# Power_Supply.net
KiCad netlist of a schematic drawn in Altium Designer
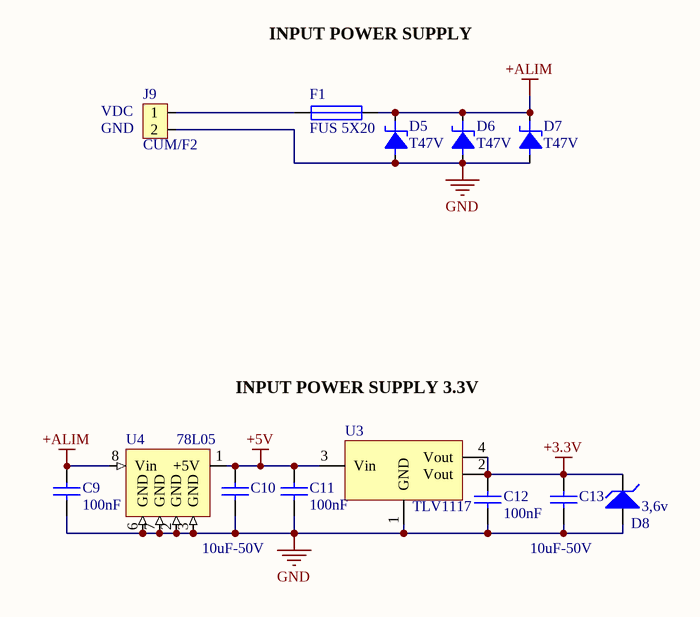
[diagram p0: Power_Supply.SchDoc]

(export (version "E")
  (design (tool "Eeschema 10.0.6"))
  (components
    (comp (ref "C9")
      (value "100nF")
      (footprint "C0603")
      (description "Capacitor")
      (libsource (lib "MyLibrary") (part "Cap"))
    )
    (comp (ref "C10")
      (value "10uF-50V")
      (footprint "C1206")
      (description "Capacitor")
      (libsource (lib "MyLibrary") (part "Cap"))
    )
    (comp (ref "C11")
      (value "100nF")
      (footprint "C0603")
      (description "Capacitor")
      (libsource (lib "MyLibrary") (part "Cap"))
    )
    (comp (ref "C12")
      (value "100nF")
      (footprint "C0603")
      (description "Capacitor")
      (libsource (lib "MyLibrary") (part "Cap"))
    )
    (comp (ref "C13")
      (value "10uF-50V")
      (footprint "C1206")
      (description "Capacitor")
      (libsource (lib "MyLibrary") (part "Cap"))
    )
    (comp (ref "D5")
      (value "T47V")
      (footprint "DIO47A")
      (description "TRANSIL CMS 47V unidirectionnelle")
      (libsource (lib "PROTEL") (part "T47V"))
    )
    (comp (ref "D6")
      (value "T47V")
      (footprint "DIO47A")
      (description "TRANSIL CMS 47V unidirectionnelle")
      (libsource (lib "PROTEL") (part "T47V"))
    )
    (comp (ref "D7")
      (value "T47V")
      (footprint "DIO47A")
      (description "TRANSIL CMS 47V unidirectionnelle")
      (libsource (lib "PROTEL") (part "T47V"))
    )
    (comp (ref "D8")
      (value "3,6v")
      (footprint "SOD123")
      (description "Zener Diode")
      (libsource (lib "MyLibrary") (part "D Zener"))
    )
    (comp (ref "F1")
      (value "FUS 5X20")
      (footprint "FUSPO-A1")
      (description "FUSIBLE VERRE 5 x 20")
      (libsource (lib "PROTEL") (part "FUS 5X20"))
    )
    (comp (ref "J9")
      (value "CUM/F2")
      (footprint "CNT2H")
      (description "connecteur  2 points")
      (libsource (lib "PROTEL") (part "CUM/F2"))
    )
    (comp (ref "U3")
      (value "TLV1117")
      (footprint "SOT223")
      (description "LDO regulator 3.3V")
      (libsource (lib "MyLibrary") (part "TLV1117"))
    )
    (comp (ref "U4")
      (value "78L05")
      (footprint "REG5VE")
      (description "E:cms ;C1:faible conso; VD:TO220 debout;")
      (libsource (lib "PROTEL") (part "78L05"))
    )
  )
  (nets
    (net (code "1") (name "+3.3V") (class "Default")
      (node (ref "C12") (pin "1") (pinfunction "1_1") (pintype "passive"))
      (node (ref "C13") (pin "2") (pinfunction "2_2") (pintype "passive"))
      (node (ref "D8") (pin "2") (pinfunction "K_2") (pintype "passive"))
      (node (ref "U3") (pin "2") (pinfunction "Vout_2") (pintype "passive"))
      (node (ref "U3") (pin "4") (pinfunction "Vout_4") (pintype "passive"))
    )
    (net (code "2") (name "+5V") (class "Default")
      (node (ref "C10") (pin "2") (pinfunction "2_2") (pintype "passive"))
      (node (ref "C11") (pin "1") (pinfunction "1_1") (pintype "passive"))
      (node (ref "U3") (pin "3") (pinfunction "Vin_3") (pintype "passive"))
      (node (ref "U4") (pin "1") (pinfunction "+5V_1") (pintype "power_in"))
    )
    (net (code "3") (name "+ALIM") (class "Default")
      (node (ref "C9") (pin "1") (pinfunction "1_1") (pintype "passive"))
      (node (ref "D5") (pin "1") (pintype "passive"))
      (node (ref "D6") (pin "1") (pintype "passive"))
      (node (ref "D7") (pin "1") (pintype "passive"))
      (node (ref "F1") (pin "2") (pintype "passive"))
      (node (ref "U4") (pin "8") (pinfunction "Vin_8") (pintype "input"))
    )
    (net (code "4") (name "GND") (class "Default")
      (node (ref "C10") (pin "1") (pinfunction "1_1") (pintype "passive"))
      (node (ref "C11") (pin "2") (pinfunction "2_2") (pintype "passive"))
      (node (ref "C12") (pin "2") (pinfunction "2_2") (pintype "passive"))
      (node (ref "C13") (pin "1") (pinfunction "1_1") (pintype "passive"))
      (node (ref "C9") (pin "2") (pinfunction "2_2") (pintype "passive"))
      (node (ref "D5") (pin "2") (pintype "passive"))
      (node (ref "D6") (pin "2") (pintype "passive"))
      (node (ref "D7") (pin "2") (pintype "passive"))
      (node (ref "D8") (pin "1") (pinfunction "A_1") (pintype "passive"))
      (node (ref "J9") (pin "2") (pinfunction "2_2") (pintype "passive"))
      (node (ref "U3") (pin "1") (pinfunction "GND_1") (pintype "power_in"))
      (node (ref "U4") (pin "2") (pinfunction "GND_2") (pintype "input"))
      (node (ref "U4") (pin "3") (pinfunction "GND_3") (pintype "input"))
      (node (ref "U4") (pin "6") (pinfunction "GND_6") (pintype "input"))
      (node (ref "U4") (pin "7") (pinfunction "GND_7") (pintype "input"))
    )
    (net (code "5") (name "Net-(F1-Pad1)") (class "Default")
      (node (ref "F1") (pin "1") (pintype "passive"))
      (node (ref "J9") (pin "1") (pinfunction "1_1") (pintype "passive"))
    )
  )
)
